# No_2.net
KiCad netlist of a schematic drawn in Altium Designer
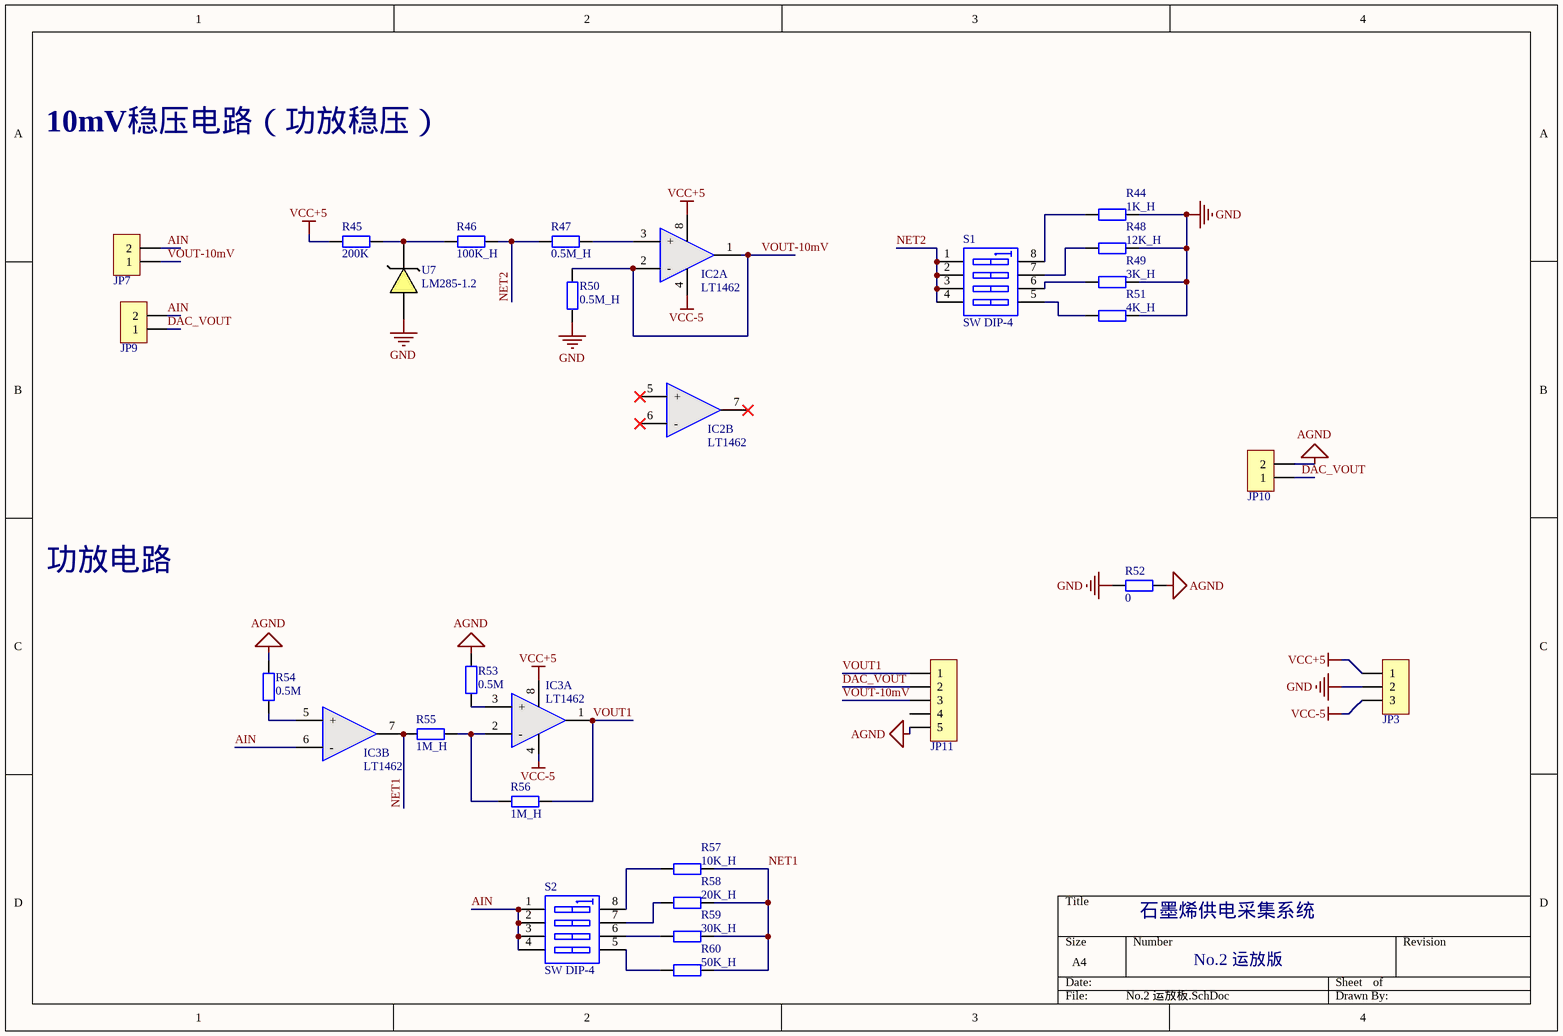
[diagram p0: No.2 运放板.SchDoc]

(export (version "E")
  (design (tool "Eeschema 10.0.6"))
  (components
    (comp (ref "IC2")
      (value "LT1462")
      (footprint "SOP8_N")
      (description "双运放")
      (fields (field (name "版权归属") "源创客"))
      (libsource (lib "1.1   - IC芯片") (part "LT1678"))
    )
    (comp (ref "IC3")
      (value "LT1462")
      (footprint "SOP8_N")
      (description "双运放")
      (fields (field (name "版权归属") "源创客"))
      (libsource (lib "1.1   - IC芯片") (part "LT1678"))
    )
    (comp (ref "JP3")
      (value "HDR-1X3")
      (footprint "XH2.54-WI-3P")
      (description "3P接插件")
      (fields (field (name "版权归属") "源创客"))
      (libsource (lib "4.2   - 接插件-脚距1.25") (part "Header 3"))
    )
    (comp (ref "JP7")
      (value "HDR-1X2")
      (footprint "XH2.54-WI-2P")
      (description "2P接插件")
      (fields (field (name "版权归属") "源创客"))
      (libsource (lib "4.5   - 接插件-脚距2.54") (part "Header 2"))
    )
    (comp (ref "JP9")
      (value "HDR-1X2")
      (footprint "XH2.54-WI-2P")
      (description "2P接插件")
      (fields (field (name "版权归属") "源创客"))
      (libsource (lib "4.5   - 接插件-脚距2.54") (part "Header 2"))
    )
    (comp (ref "JP10")
      (value "HDR-1X2")
      (footprint "XH2.54-WI-2P")
      (description "2P接插件")
      (fields (field (name "版权归属") "源创客"))
      (libsource (lib "4.5   - 接插件-脚距2.54") (part "Header 2"))
    )
    (comp (ref "JP11")
      (value "HDR-1X5")
      (footprint "XH2.54-WI-5P")
      (description "5P接插件")
      (fields (field (name "版权归属") "源创客"))
      (libsource (lib "4.5   - 接插件-脚距2.54") (part "Header 5"))
    )
    (comp (ref "R44")
      (value "1K_H")
      (footprint "RS 1/4W")
      (description "贴片电阻")
      (fields (field (name "版权归属") "源创客"))
      (libsource (lib "3.1   - 电阻-电容-电感") (part "R"))
    )
    (comp (ref "R45")
      (value "200K")
      (footprint "R 0805_M")
      (description "贴片电阻")
      (fields (field (name "版权归属") "源创客"))
      (libsource (lib "3.1   - 电阻-电容-电感") (part "R"))
    )
    (comp (ref "R46")
      (value "100K_H")
      (footprint "RS 1/4W")
      (description "贴片电阻")
      (fields (field (name "版权归属") "源创客"))
      (libsource (lib "3.1   - 电阻-电容-电感") (part "R"))
    )
    (comp (ref "R47")
      (value "0.5M_H")
      (footprint "RS 1/4W")
      (description "贴片电阻")
      (fields (field (name "版权归属") "源创客"))
      (libsource (lib "3.1   - 电阻-电容-电感") (part "R"))
    )
    (comp (ref "R48")
      (value "12K_H")
      (footprint "RS 1/4W")
      (description "贴片电阻")
      (fields (field (name "版权归属") "源创客"))
      (libsource (lib "3.1   - 电阻-电容-电感") (part "R"))
    )
    (comp (ref "R49")
      (value "3K_H")
      (footprint "RS 1/4W")
      (description "贴片电阻")
      (fields (field (name "版权归属") "源创客"))
      (libsource (lib "3.1   - 电阻-电容-电感") (part "R"))
    )
    (comp (ref "R50")
      (value "0.5M_H")
      (footprint "RS 1/4W")
      (description "贴片电阻")
      (fields (field (name "版权归属") "源创客"))
      (libsource (lib "3.1   - 电阻-电容-电感") (part "R"))
    )
    (comp (ref "R51")
      (value "4K_H")
      (footprint "RS 1/4W")
      (description "贴片电阻")
      (fields (field (name "版权归属") "源创客"))
      (libsource (lib "3.1   - 电阻-电容-电感") (part "R"))
    )
    (comp (ref "R52")
      (value "0")
      (footprint "R 0805_M")
      (description "贴片电阻")
      (fields (field (name "版权归属") "源创客"))
      (libsource (lib "3.1   - 电阻-电容-电感") (part "R"))
    )
    (comp (ref "R53")
      (value "0.5M")
      (footprint "R 0805_M")
      (description "贴片电阻")
      (fields (field (name "版权归属") "源创客"))
      (libsource (lib "3.1   - 电阻-电容-电感") (part "R"))
    )
    (comp (ref "R54")
      (value "0.5M")
      (footprint "R 0805_M")
      (description "贴片电阻")
      (fields (field (name "版权归属") "源创客"))
      (libsource (lib "3.1   - 电阻-电容-电感") (part "R"))
    )
    (comp (ref "R55")
      (value "1M_H")
      (footprint "RS 1/4W")
      (description "贴片电阻")
      (fields (field (name "版权归属") "源创客"))
      (libsource (lib "3.1   - 电阻-电容-电感") (part "R"))
    )
    (comp (ref "R56")
      (value "1M_H")
      (footprint "RS 1/4W")
      (description "贴片电阻")
      (fields (field (name "版权归属") "源创客"))
      (libsource (lib "3.1   - 电阻-电容-电感") (part "R"))
    )
    (comp (ref "R57")
      (value "10K_H")
      (footprint "RS 1/4W")
      (description "贴片电阻")
      (fields (field (name "版权归属") "源创客"))
      (libsource (lib "3.1   - 电阻-电容-电感") (part "R"))
    )
    (comp (ref "R58")
      (value "20K_H")
      (footprint "RS 1/4W")
      (description "贴片电阻")
      (fields (field (name "版权归属") "源创客"))
      (libsource (lib "3.1   - 电阻-电容-电感") (part "R"))
    )
    (comp (ref "R59")
      (value "30K_H")
      (footprint "RS 1/4W")
      (description "贴片电阻")
      (fields (field (name "版权归属") "源创客"))
      (libsource (lib "3.1   - 电阻-电容-电感") (part "R"))
    )
    (comp (ref "R60")
      (value "50K_H")
      (footprint "RS 1/4W")
      (description "贴片电阻")
      (fields (field (name "版权归属") "源创客"))
      (libsource (lib "3.1   - 电阻-电容-电感") (part "R"))
    )
    (comp (ref "S1")
      (value "SW DIP-4")
      (footprint "SO-8M")
      (description "DIP Switch, 4 Position, SPST")
      (fields (field (name "PUBLISHER") "Altium Limited"))
      (libsource (lib "开关及电源") (part "SW DIP-4"))
    )
    (comp (ref "S2")
      (value "SW DIP-4")
      (footprint "SO-8M")
      (description "DIP Switch, 4 Position, SPST")
      (fields (field (name "PUBLISHER") "Altium Limited"))
      (libsource (lib "开关及电源") (part "SW DIP-4"))
    )
    (comp (ref "U7") (value "LM285-1.2") (footprint "TO92A") (libsource (lib "Schlib1") (part "LM285-1.2")))
  )
  (nets
    (net (code "1") (name "/AIN") (class "Default")
      (node (ref "IC3") (pin "6") (pinfunction "-_6") (pintype "passive"))
      (node (ref "JP7") (pin "2") (pinfunction "2_2") (pintype "passive"))
      (node (ref "JP9") (pin "2") (pinfunction "2_2") (pintype "passive"))
      (node (ref "S2") (pin "1") (pinfunction "A1_1") (pintype "passive"))
      (node (ref "S2") (pin "2") (pinfunction "A2_2") (pintype "passive"))
      (node (ref "S2") (pin "3") (pinfunction "A3_3") (pintype "passive"))
      (node (ref "S2") (pin "4") (pinfunction "A4_4") (pintype "passive"))
    )
    (net (code "2") (name "/DAC_VOUT") (class "Default")
      (node (ref "JP10") (pin "1") (pinfunction "1_1") (pintype "passive"))
      (node (ref "JP11") (pin "2") (pinfunction "2_2") (pintype "passive"))
      (node (ref "JP9") (pin "1") (pinfunction "1_1") (pintype "passive"))
    )
    (net (code "3") (name "/NET1") (class "Default")
      (node (ref "IC3") (pin "7") (pinfunction "OUT2_7") (pintype "passive"))
      (node (ref "R55") (pin "1") (pinfunction "1_1") (pintype "passive"))
      (node (ref "R57") (pin "2") (pinfunction "2_2") (pintype "passive"))
      (node (ref "R58") (pin "2") (pinfunction "2_2") (pintype "passive"))
      (node (ref "R59") (pin "2") (pinfunction "2_2") (pintype "passive"))
      (node (ref "R60") (pin "2") (pinfunction "2_2") (pintype "passive"))
    )
    (net (code "4") (name "/NET2") (class "Default")
      (node (ref "R46") (pin "2") (pinfunction "2_2") (pintype "passive"))
      (node (ref "R47") (pin "1") (pinfunction "1_1") (pintype "passive"))
      (node (ref "S1") (pin "1") (pinfunction "A1_1") (pintype "passive"))
      (node (ref "S1") (pin "2") (pinfunction "A2_2") (pintype "passive"))
      (node (ref "S1") (pin "3") (pinfunction "A3_3") (pintype "passive"))
      (node (ref "S1") (pin "4") (pinfunction "A4_4") (pintype "passive"))
    )
    (net (code "5") (name "/VOUT-10mV") (class "Default")
      (node (ref "IC2") (pin "1") (pinfunction "OUT1_1") (pintype "passive"))
      (node (ref "IC2") (pin "2") (pinfunction "-_2") (pintype "passive"))
      (node (ref "JP11") (pin "3") (pinfunction "3_3") (pintype "passive"))
      (node (ref "JP7") (pin "1") (pinfunction "1_1") (pintype "passive"))
      (node (ref "R50") (pin "2") (pinfunction "2_2") (pintype "passive"))
    )
    (net (code "6") (name "/VOUT1") (class "Default")
      (node (ref "IC3") (pin "1") (pinfunction "OUT1_1") (pintype "passive"))
      (node (ref "JP11") (pin "1") (pinfunction "1_1") (pintype "passive"))
      (node (ref "R56") (pin "2") (pinfunction "2_2") (pintype "passive"))
    )
    (net (code "7") (name "AGND") (class "Default")
      (node (ref "JP10") (pin "2") (pinfunction "2_2") (pintype "passive"))
      (node (ref "JP11") (pin "5") (pinfunction "5_5") (pintype "passive"))
      (node (ref "R52") (pin "2") (pinfunction "2_2") (pintype "passive"))
      (node (ref "R53") (pin "1") (pinfunction "1_1") (pintype "passive"))
      (node (ref "R54") (pin "1") (pinfunction "1_1") (pintype "passive"))
    )
    (net (code "8") (name "GND") (class "Default")
      (node (ref "JP3") (pin "2") (pinfunction "2_2") (pintype "passive"))
      (node (ref "R44") (pin "2") (pinfunction "2_2") (pintype "passive"))
      (node (ref "R48") (pin "2") (pinfunction "2_2") (pintype "passive"))
      (node (ref "R49") (pin "2") (pinfunction "2_2") (pintype "passive"))
      (node (ref "R50") (pin "1") (pinfunction "1_1") (pintype "passive"))
      (node (ref "R51") (pin "2") (pinfunction "2_2") (pintype "passive"))
      (node (ref "R52") (pin "1") (pinfunction "1_1") (pintype "passive"))
      (node (ref "U7") (pin "3") (pinfunction "ANODE_3") (pintype "passive"))
    )
    (net (code "9") (name "Net-(IC2A-+)") (class "Default")
      (node (ref "IC2") (pin "3") (pinfunction "+_3") (pintype "passive"))
      (node (ref "R47") (pin "2") (pinfunction "2_2") (pintype "passive"))
    )
    (net (code "10") (name "Net-(IC3A-+)") (class "Default")
      (node (ref "IC3") (pin "3") (pinfunction "+_3") (pintype "passive"))
      (node (ref "R53") (pin "2") (pinfunction "2_2") (pintype "passive"))
    )
    (net (code "11") (name "Net-(IC3A--)") (class "Default")
      (node (ref "IC3") (pin "2") (pinfunction "-_2") (pintype "passive"))
      (node (ref "R55") (pin "2") (pinfunction "2_2") (pintype "passive"))
      (node (ref "R56") (pin "1") (pinfunction "1_1") (pintype "passive"))
    )
    (net (code "12") (name "Net-(IC3B-+)") (class "Default")
      (node (ref "IC3") (pin "5") (pinfunction "+_5") (pintype "passive"))
      (node (ref "R54") (pin "2") (pinfunction "2_2") (pintype "passive"))
    )
    (net (code "13") (name "Net-(S1-B1)") (class "Default")
      (node (ref "R44") (pin "1") (pinfunction "1_1") (pintype "passive"))
      (node (ref "S1") (pin "8") (pinfunction "B1_8") (pintype "passive"))
    )
    (net (code "14") (name "Net-(S1-B2)") (class "Default")
      (node (ref "R48") (pin "1") (pinfunction "1_1") (pintype "passive"))
      (node (ref "S1") (pin "7") (pinfunction "B2_7") (pintype "passive"))
    )
    (net (code "15") (name "Net-(S1-B3)") (class "Default")
      (node (ref "R49") (pin "1") (pinfunction "1_1") (pintype "passive"))
      (node (ref "S1") (pin "6") (pinfunction "B3_6") (pintype "passive"))
    )
    (net (code "16") (name "Net-(S1-B4)") (class "Default")
      (node (ref "R51") (pin "1") (pinfunction "1_1") (pintype "passive"))
      (node (ref "S1") (pin "5") (pinfunction "B4_5") (pintype "passive"))
    )
    (net (code "17") (name "Net-(S2-B1)") (class "Default")
      (node (ref "R57") (pin "1") (pinfunction "1_1") (pintype "passive"))
      (node (ref "S2") (pin "8") (pinfunction "B1_8") (pintype "passive"))
    )
    (net (code "18") (name "Net-(S2-B2)") (class "Default")
      (node (ref "R58") (pin "1") (pinfunction "1_1") (pintype "passive"))
      (node (ref "S2") (pin "7") (pinfunction "B2_7") (pintype "passive"))
    )
    (net (code "19") (name "Net-(S2-B3)") (class "Default")
      (node (ref "R59") (pin "1") (pinfunction "1_1") (pintype "passive"))
      (node (ref "S2") (pin "6") (pinfunction "B3_6") (pintype "passive"))
    )
    (net (code "20") (name "Net-(S2-B4)") (class "Default")
      (node (ref "R60") (pin "1") (pinfunction "1_1") (pintype "passive"))
      (node (ref "S2") (pin "5") (pinfunction "B4_5") (pintype "passive"))
    )
    (net (code "21") (name "Net-(U7-CATHODE)") (class "Default")
      (node (ref "R45") (pin "2") (pinfunction "2_2") (pintype "passive"))
      (node (ref "R46") (pin "1") (pinfunction "1_1") (pintype "passive"))
      (node (ref "U7") (pin "2") (pinfunction "CATHODE_2") (pintype "passive"))
    )
    (net (code "22") (name "VCC+5") (class "Default")
      (node (ref "IC2") (pin "8") (pinfunction "V+_8") (pintype "power_in"))
      (node (ref "IC3") (pin "8") (pinfunction "V+_8") (pintype "power_in"))
      (node (ref "JP3") (pin "1") (pinfunction "1_1") (pintype "passive"))
      (node (ref "R45") (pin "1") (pinfunction "1_1") (pintype "passive"))
    )
    (net (code "23") (name "VCC-5") (class "Default")
      (node (ref "IC2") (pin "4") (pinfunction "V-_4") (pintype "power_in"))
      (node (ref "IC3") (pin "4") (pinfunction "V-_4") (pintype "power_in"))
      (node (ref "JP3") (pin "3") (pinfunction "3_3") (pintype "passive"))
    )
    (net (code "24") (name "unconnected-(IC2B-+-Pad5)") (class "Default")
      (node (ref "IC2") (pin "5") (pinfunction "+_5") (pintype "passive+no_connect"))
    )
    (net (code "25") (name "unconnected-(IC2B---Pad6)") (class "Default")
      (node (ref "IC2") (pin "6") (pinfunction "-_6") (pintype "passive+no_connect"))
    )
    (net (code "26") (name "unconnected-(IC2B-OUT2-Pad7)") (class "Default")
      (node (ref "IC2") (pin "7") (pinfunction "OUT2_7") (pintype "passive+no_connect"))
    )
    (net (code "27") (name "unconnected-(JP11-Pad4)") (class "Default")
      (node (ref "JP11") (pin "4") (pinfunction "4_4") (pintype "passive"))
    )
  )
)
